# KKK_valdiklis_kopija.net
KiCad netlist of a schematic drawn in EAGLE
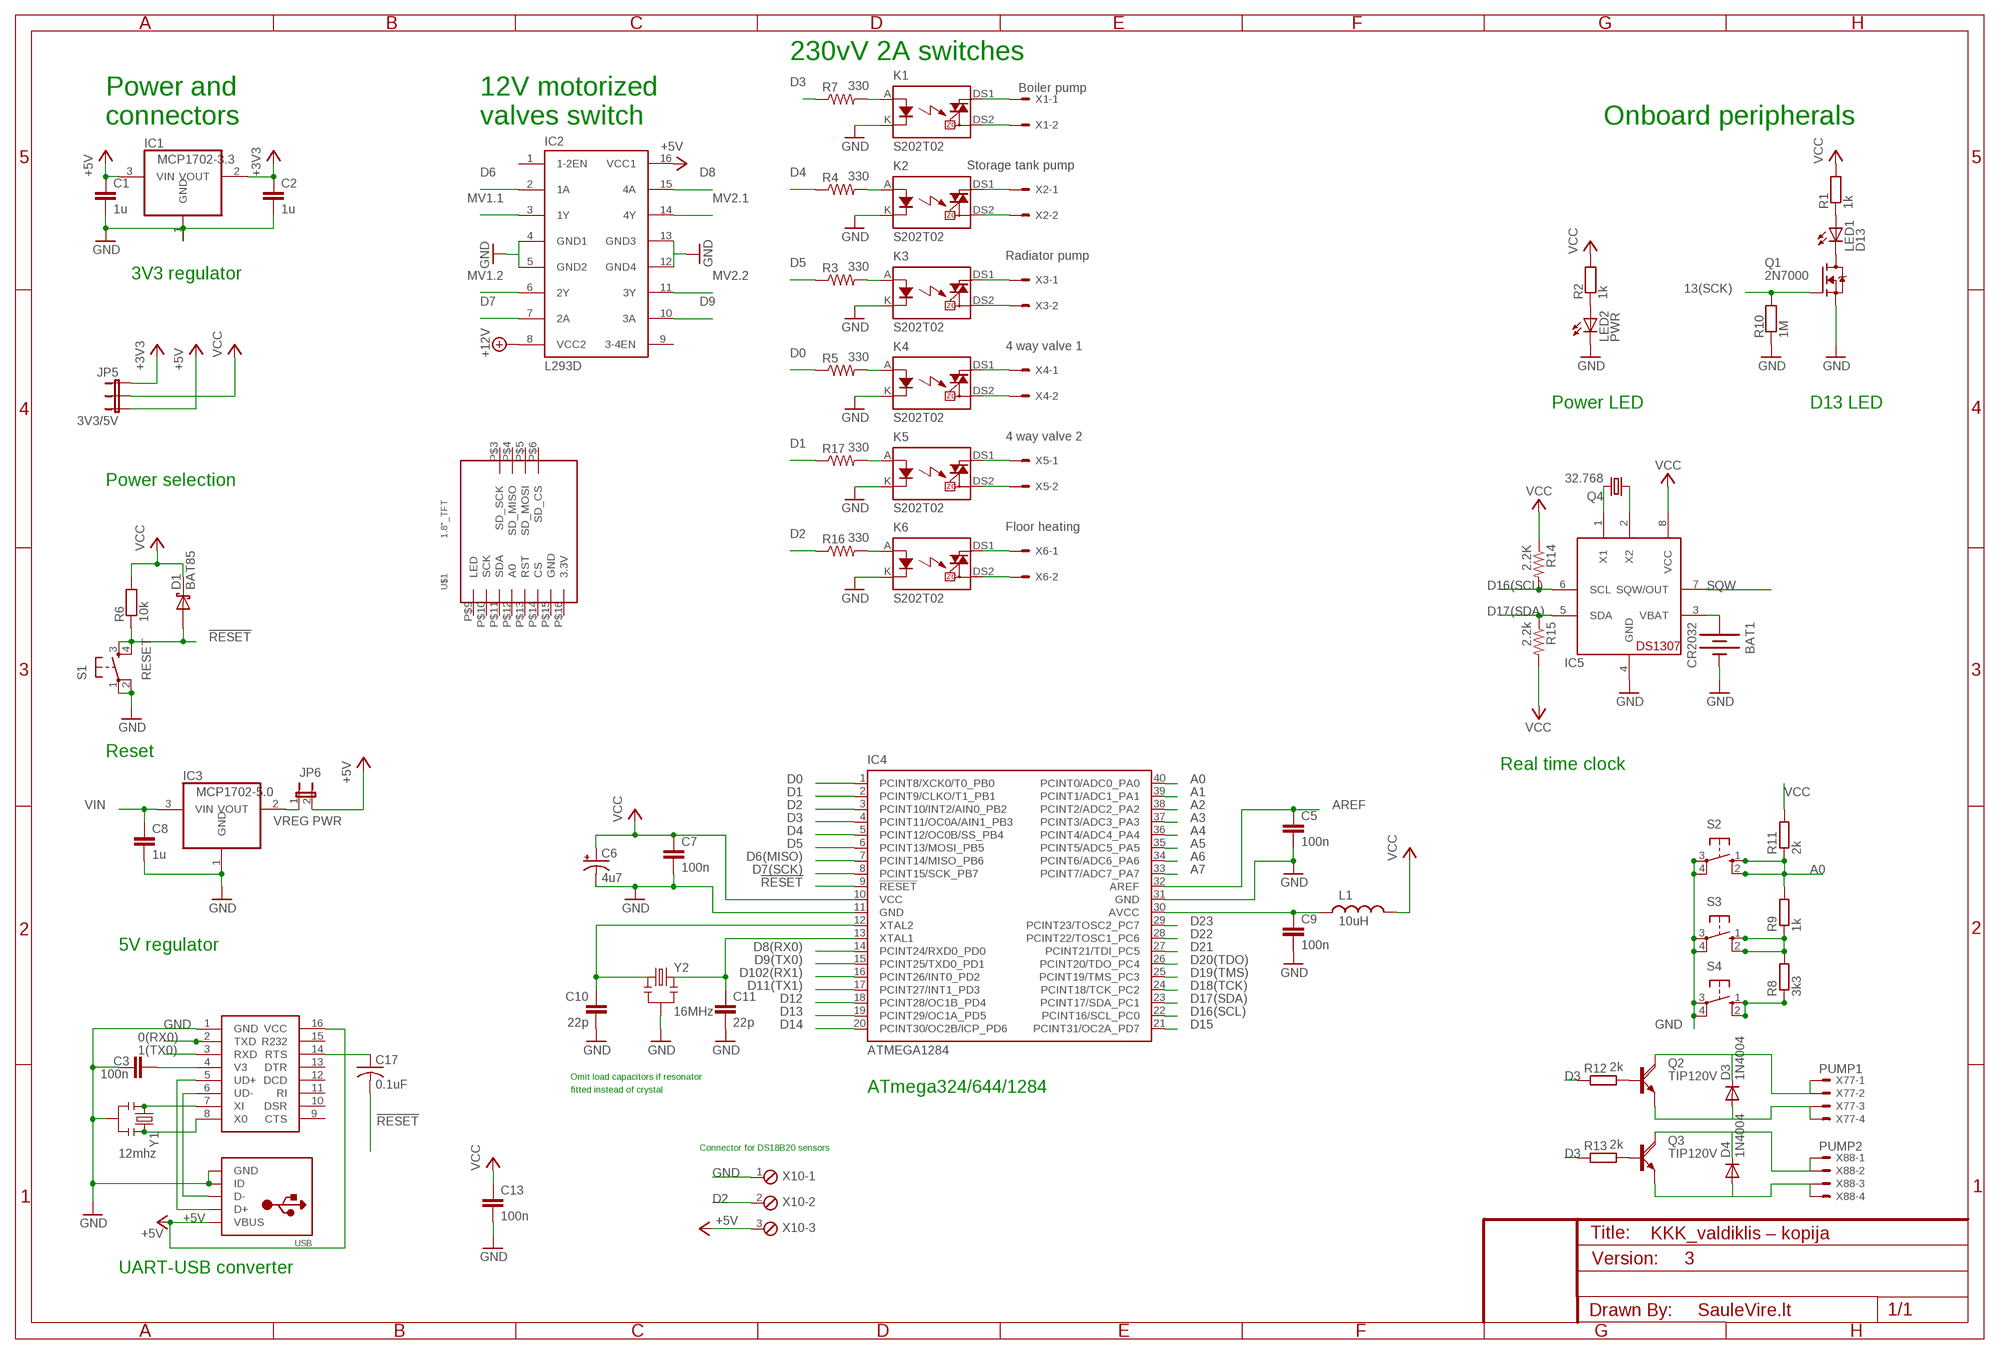
[diagram p0: schematic, sheet 1]

(export (version "E")
  (design (tool "Eeschema 10.0.6"))
  (components
    (comp (ref "BAT1")
      (value "CR2032")
      (footprint "eagle-import:BATTCOM_20MM_PTH")
      (libsource (lib "eagle-import") (part "BATTERY20PTH"))
    )
    (comp (ref "C1")
      (value "1u")
      (footprint "eagle-import:CAP-PTH-5MM")
      (libsource (lib "eagle-import") (part "CAPPTH1"))
    )
    (comp (ref "C2")
      (value "1u")
      (footprint "eagle-import:CAP-PTH-5MM")
      (libsource (lib "eagle-import") (part "CAPPTH1"))
    )
    (comp (ref "C3")
      (value "100n")
      (footprint "eagle-import:CAP-PTH-SMALL")
      (libsource (lib "eagle-import") (part "CAPPTH"))
    )
    (comp (ref "C5")
      (value "100n")
      (footprint "eagle-import:CAP-PTH-SMALL")
      (libsource (lib "eagle-import") (part "CAPPTH"))
    )
    (comp (ref "C6")
      (value "4u7")
      (footprint "eagle-import:CPOL-RADIAL-10UF-25V")
      (libsource (lib "eagle-import") (part "CAP_POLPTH2"))
    )
    (comp (ref "C7")
      (value "100n")
      (footprint "eagle-import:CAP-PTH-SMALL")
      (libsource (lib "eagle-import") (part "CAPPTH"))
    )
    (comp (ref "C8")
      (value "1u")
      (footprint "eagle-import:CAP-PTH-5MM")
      (libsource (lib "eagle-import") (part "CAPPTH1"))
    )
    (comp (ref "C9")
      (value "100n")
      (footprint "eagle-import:CAP-PTH-SMALL")
      (libsource (lib "eagle-import") (part "CAPPTH"))
    )
    (comp (ref "C10")
      (value "22p")
      (footprint "eagle-import:CAP-PTH-SMALL")
      (libsource (lib "eagle-import") (part "CAPPTH"))
    )
    (comp (ref "C11")
      (value "22p")
      (footprint "eagle-import:CAP-PTH-SMALL")
      (libsource (lib "eagle-import") (part "CAPPTH"))
    )
    (comp (ref "C13")
      (value "100n")
      (footprint "eagle-import:CAP-PTH-SMALL")
      (libsource (lib "eagle-import") (part "CAPPTH"))
    )
    (comp (ref "C17")
      (value "0.1uF")
      (footprint "eagle-import:C0805K")
      (libsource (lib "eagle-import") (part "C-USC0805K"))
    )
    (comp (ref "D1")
      (value "BAT85")
      (footprint "eagle-import:DIODE-TH-0.4")
      (libsource (lib "eagle-import") (part "DIODE-SCHOTTKY"))
    )
    (comp (ref "D3")
      (value "1N4004")
      (footprint "eagle-import:DO41-10")
      (libsource (lib "eagle-import") (part "1N4004"))
    )
    (comp (ref "D4")
      (value "1N4004")
      (footprint "eagle-import:DO41-10")
      (libsource (lib "eagle-import") (part "1N4004"))
    )
    (comp (ref "IC1")
      (value "MCP1702-3.3")
      (footprint "eagle-import:SOT223")
      (fields (field (name "MPN") "REG1117"))
      (libsource (lib "eagle-import") (part "REG1117"))
    )
    (comp (ref "IC2")
      (value "L293D")
      (footprint "eagle-import:DIL16")
      (libsource (lib "eagle-import") (part "L293D"))
    )
    (comp (ref "IC3")
      (value "MCP1702-5.0")
      (footprint "eagle-import:SOT223")
      (fields (field (name "MPN") "REG1117"))
      (libsource (lib "eagle-import") (part "REG1117"))
    )
    (comp (ref "IC4")
      (value "ATMEGA1284")
      (footprint "eagle-import:DIL40")
      (fields (field (name "MPN") "ATMEGA644-20PU"))
      (libsource (lib "eagle-import") (part "ATMEGA644-PU20"))
    )
    (comp (ref "IC5")
      (value "DS1307")
      (footprint "eagle-import:DIL08")
      (libsource (lib "eagle-import") (part "DS1307"))
    )
    (comp (ref "JP5")
      (value "3V3/5V")
      (footprint "eagle-import:1X03")
      (libsource (lib "eagle-import") (part "JUMPER-3PTH"))
    )
    (comp (ref "JP6")
      (value "VREG PWR")
      (footprint "eagle-import:1X02")
      (libsource (lib "eagle-import") (part "JUMPER-2PTH"))
    )
    (comp (ref "K1")
      (value "S202T02")
      (footprint "eagle-import:S202T02")
      (libsource (lib "eagle-import") (part "S202T02"))
    )
    (comp (ref "K2")
      (value "S202T02")
      (footprint "eagle-import:S202T02")
      (libsource (lib "eagle-import") (part "S202T02"))
    )
    (comp (ref "K3")
      (value "S202T02")
      (footprint "eagle-import:S202T02")
      (libsource (lib "eagle-import") (part "S202T02"))
    )
    (comp (ref "K4")
      (value "S202T02")
      (footprint "eagle-import:S202T02")
      (libsource (lib "eagle-import") (part "S202T02"))
    )
    (comp (ref "K5")
      (value "S202T02")
      (footprint "eagle-import:S202T02")
      (libsource (lib "eagle-import") (part "S202T02"))
    )
    (comp (ref "K6")
      (value "S202T02")
      (footprint "eagle-import:S202T02")
      (libsource (lib "eagle-import") (part "S202T02"))
    )
    (comp (ref "L1")
      (value "10uH")
      (footprint "eagle-import:RES-AXIAL-0.4")
      (libsource (lib "eagle-import") (part "INDUCTOR0.4{dblquote}-AXIAL"))
    )
    (comp (ref "LED1")
      (value "D13")
      (footprint "eagle-import:LED3MM")
      (libsource (lib "eagle-import") (part "LED3MM"))
    )
    (comp (ref "LED2")
      (value "PWR")
      (footprint "eagle-import:LED3MM")
      (libsource (lib "eagle-import") (part "LED3MM"))
    )
    (comp (ref "Q1")
      (value "2N7000")
      (footprint "eagle-import:TO-92")
      (libsource (lib "eagle-import") (part "2N7000"))
    )
    (comp (ref "Q2")
      (value "TIP120V")
      (footprint "eagle-import:TO220AV")
      (libsource (lib "eagle-import") (part "TIP120V"))
    )
    (comp (ref "Q3")
      (value "TIP120V")
      (footprint "eagle-import:TO220AV")
      (libsource (lib "eagle-import") (part "TIP120V"))
    )
    (comp (ref "Q4")
      (value "32.768")
      (footprint "eagle-import:TC38H")
      (libsource (lib "eagle-import") (part "CRYTALTC38H"))
    )
    (comp (ref "R1")
      (value "1k")
      (footprint "eagle-import:RES-AXIAL-0.4")
      (libsource (lib "eagle-import") (part "RESISTOR"))
    )
    (comp (ref "R2")
      (value "1k")
      (footprint "eagle-import:RES-AXIAL-0.4")
      (libsource (lib "eagle-import") (part "RESISTOR"))
    )
    (comp (ref "R3")
      (value "330")
      (footprint "eagle-import:0207_10")
      (libsource (lib "eagle-import") (part "resistor-1_R-US_0207/10"))
    )
    (comp (ref "R4")
      (value "330")
      (footprint "eagle-import:0207_10")
      (libsource (lib "eagle-import") (part "resistor-1_R-US_0207/10"))
    )
    (comp (ref "R5")
      (value "330")
      (footprint "eagle-import:0207_10")
      (libsource (lib "eagle-import") (part "resistor-1_R-US_0207/10"))
    )
    (comp (ref "R6")
      (value "10k")
      (footprint "eagle-import:RES-AXIAL-0.4")
      (libsource (lib "eagle-import") (part "RESISTOR"))
    )
    (comp (ref "R7")
      (value "330")
      (footprint "eagle-import:0207_10")
      (libsource (lib "eagle-import") (part "resistor-1_R-US_0207/10"))
    )
    (comp (ref "R8")
      (value "3k3")
      (footprint "eagle-import:0207_10")
      (libsource (lib "eagle-import") (part "R-EU_0207/10"))
    )
    (comp (ref "R9")
      (value "1k")
      (footprint "eagle-import:0207_10")
      (libsource (lib "eagle-import") (part "R-EU_0207/10"))
    )
    (comp (ref "R10")
      (value "1M")
      (footprint "eagle-import:RES-AXIAL-0.4")
      (libsource (lib "eagle-import") (part "RESISTOR"))
    )
    (comp (ref "R11")
      (value "2k")
      (footprint "eagle-import:0207_10")
      (libsource (lib "eagle-import") (part "R-EU_0207/10"))
    )
    (comp (ref "R12")
      (value "2k")
      (footprint "eagle-import:0207_10")
      (libsource (lib "eagle-import") (part "R-EU_0207/10"))
    )
    (comp (ref "R13")
      (value "2k")
      (footprint "eagle-import:0207_10")
      (libsource (lib "eagle-import") (part "R-EU_0207/10"))
    )
    (comp (ref "R14")
      (value "2.2K")
      (footprint "eagle-import:0207_10")
      (libsource (lib "eagle-import") (part "R-US_0207/10"))
    )
    (comp (ref "R15")
      (value "2.2k")
      (footprint "eagle-import:0207_10")
      (libsource (lib "eagle-import") (part "R-US_0207/10"))
    )
    (comp (ref "R16")
      (value "330")
      (footprint "eagle-import:0207_10")
      (libsource (lib "eagle-import") (part "resistor-1_R-US_0207/10"))
    )
    (comp (ref "R17")
      (value "330")
      (footprint "eagle-import:0207_10")
      (libsource (lib "eagle-import") (part "resistor-1_R-US_0207/10"))
    )
    (comp (ref "S1")
      (value "RESET")
      (footprint "eagle-import:TACTILE-PTH")
      (libsource (lib "eagle-import") (part "TAC_SWITCHPTH"))
    )
    (comp (ref "S2")
      (value "10-XX")
      (footprint "eagle-import:B3F-10XX")
      (fields (field (name "MPN") "B3F-1000"))
      (libsource (lib "eagle-import") (part "10-XX"))
    )
    (comp (ref "S3")
      (value "10-XX")
      (footprint "eagle-import:B3F-10XX")
      (fields (field (name "MPN") "B3F-1000"))
      (libsource (lib "eagle-import") (part "10-XX"))
    )
    (comp (ref "S4")
      (value "10-XX")
      (footprint "eagle-import:B3F-10XX")
      (fields (field (name "MPN") "B3F-1000"))
      (libsource (lib "eagle-import") (part "10-XX"))
    )
    (comp (ref "U$1")
      (value "1.8\"_TFT")
      (footprint "eagle-import:1.8__TFT")
      (libsource (lib "eagle-import") (part "1.8{dblquote}_TFT"))
    )
    (comp (ref "U$2")
      (value "CH340G")
      (footprint "eagle-import:SO016")
      (libsource (lib "eagle-import") (part "CH340G"))
    )
    (comp (ref "USB")
      (value "USBMOLEX")
      (footprint "eagle-import:USB-MINIB-THM-MOLEX")
      (libsource (lib "eagle-import") (part "USBMOLEX"))
    )
    (comp (ref "X1")
      (value "Boiler pump")
      (footprint "eagle-import:22-23-2021")
      (fields (field (name "MF") "MOLEX") (field (name "MPN") "22-23-2021"))
      (libsource (lib "eagle-import") (part "22-23-2021"))
    )
    (comp (ref "X2")
      (value "Storage tank pump")
      (footprint "eagle-import:22-23-2021")
      (fields (field (name "MF") "MOLEX") (field (name "MPN") "22-23-2021"))
      (libsource (lib "eagle-import") (part "22-23-2021"))
    )
    (comp (ref "X3")
      (value "Radiator pump")
      (footprint "eagle-import:22-23-2021")
      (fields (field (name "MF") "MOLEX") (field (name "MPN") "22-23-2021"))
      (libsource (lib "eagle-import") (part "22-23-2021"))
    )
    (comp (ref "X4")
      (value "4 way valve 1")
      (footprint "eagle-import:22-23-2021")
      (fields (field (name "MF") "MOLEX") (field (name "MPN") "22-23-2021"))
      (libsource (lib "eagle-import") (part "22-23-2021"))
    )
    (comp (ref "X5")
      (value "4 way valve 2")
      (footprint "eagle-import:22-23-2021")
      (fields (field (name "MF") "MOLEX") (field (name "MPN") "22-23-2021"))
      (libsource (lib "eagle-import") (part "22-23-2021"))
    )
    (comp (ref "X6")
      (value "Floor heating")
      (footprint "eagle-import:22-23-2021")
      (fields (field (name "MF") "MOLEX") (field (name "MPN") "22-23-2021"))
      (libsource (lib "eagle-import") (part "22-23-2021"))
    )
    (comp (ref "X10")
      (value "MPT3")
      (footprint "eagle-import:3POL254")
      (libsource (lib "eagle-import") (part "MPT3"))
    )
    (comp (ref "X77")
      (value "PUMP1")
      (footprint "eagle-import:22-23-2041")
      (fields (field (name "MF") "MOLEX") (field (name "MPN") "22-23-2041"))
      (libsource (lib "eagle-import") (part "22-23-2041"))
    )
    (comp (ref "X88")
      (value "PUMP2")
      (footprint "eagle-import:22-23-2041")
      (fields (field (name "MF") "MOLEX") (field (name "MPN") "22-23-2041"))
      (libsource (lib "eagle-import") (part "22-23-2041"))
    )
    (comp (ref "Y1")
      (value "12mhz")
      (footprint "eagle-import:RESONATOR-PTH")
      (libsource (lib "eagle-import") (part "RESONATORPTH"))
    )
    (comp (ref "Y2")
      (value "16MHz")
      (footprint "eagle-import:HC49U-V-RESONATOR")
      (libsource (lib "eagle-import") (part "CRYSTAL-RESONATOR"))
    )
  )
  (nets
    (net (code "1") (name "+3V3") (class "Default")
      (node (ref "C2") (pin "1") (pinfunction "1_1") (pintype "passive"))
      (node (ref "IC1") (pin "2") (pinfunction "VOUT_2") (pintype "output"))
      (node (ref "JP5") (pin "1") (pinfunction "1_1") (pintype "passive"))
    )
    (net (code "2") (name "+5V") (class "Default")
      (node (ref "C1") (pin "1") (pinfunction "1_1") (pintype "passive"))
      (node (ref "IC1") (pin "3") (pinfunction "VIN_3") (pintype "input"))
      (node (ref "IC2") (pin "16") (pinfunction "VCC1_16") (pintype "power_in"))
      (node (ref "JP5") (pin "3") (pinfunction "3_3") (pintype "passive"))
      (node (ref "JP6") (pin "2") (pinfunction "2_2") (pintype "passive"))
      (node (ref "U$2") (pin "16") (pinfunction "VCC_16") (pintype "bidirectional"))
      (node (ref "USB") (pin "VBUS") (pinfunction "VBUS_VBUS") (pintype "power_in"))
      (node (ref "X10") (pin "3") (pinfunction "1_3") (pintype "passive"))
    )
    (net (code "3") (name "+12V") (class "Default")
      (node (ref "IC2") (pin "8") (pinfunction "VCC2_8") (pintype "power_in"))
    )
    (net (code "4") (name "/0(RX0)") (class "Default")
      (node (ref "U$2") (pin "2") (pinfunction "TXD_2") (pintype "bidirectional"))
    )
    (net (code "5") (name "/1(TX0)") (class "Default")
      (node (ref "U$2") (pin "3") (pinfunction "RXD_3") (pintype "bidirectional"))
    )
    (net (code "6") (name "/13(SCK)") (class "Default")
      (node (ref "Q1") (pin "2") (pinfunction "G_2") (pintype "passive"))
      (node (ref "R10") (pin "P$2") (pinfunction "2_P$2") (pintype "passive"))
    )
    (net (code "7") (name "/A0") (class "Default")
      (node (ref "IC4") (pin "40") (pinfunction "PCINT0/ADC0_PA0_40") (pintype "bidirectional"))
      (node (ref "R11") (pin "1") (pinfunction "1_1") (pintype "passive"))
      (node (ref "R9") (pin "2") (pinfunction "2_2") (pintype "passive"))
      (node (ref "S2") (pin "1") (pinfunction "S_1") (pintype "passive"))
      (node (ref "S2") (pin "2") (pinfunction "S1_2") (pintype "passive"))
    )
    (net (code "8") (name "/A1") (class "Default")
      (node (ref "IC4") (pin "39") (pinfunction "PCINT1/ADC1_PA1_39") (pintype "bidirectional"))
    )
    (net (code "9") (name "/A2") (class "Default")
      (node (ref "IC4") (pin "38") (pinfunction "PCINT2/ADC2_PA2_38") (pintype "bidirectional"))
    )
    (net (code "10") (name "/A3") (class "Default")
      (node (ref "IC4") (pin "37") (pinfunction "PCINT3/ADC3_PA3_37") (pintype "bidirectional"))
    )
    (net (code "11") (name "/A4") (class "Default")
      (node (ref "IC4") (pin "36") (pinfunction "PCINT4/ADC4_PA4_36") (pintype "bidirectional"))
    )
    (net (code "12") (name "/A5") (class "Default")
      (node (ref "IC4") (pin "35") (pinfunction "PCINT5/ADC5_PA5_35") (pintype "bidirectional"))
    )
    (net (code "13") (name "/A6") (class "Default")
      (node (ref "IC4") (pin "34") (pinfunction "PCINT6/ADC6_PA6_34") (pintype "bidirectional"))
    )
    (net (code "14") (name "/A7") (class "Default")
      (node (ref "IC4") (pin "33") (pinfunction "PCINT7/ADC7_PA7_33") (pintype "bidirectional"))
    )
    (net (code "15") (name "/AREF") (class "Default")
      (node (ref "C5") (pin "1") (pinfunction "1_1") (pintype "passive"))
      (node (ref "IC4") (pin "32") (pinfunction "AREF_32") (pintype "passive"))
    )
    (net (code "16") (name "/D0") (class "Default")
      (node (ref "IC4") (pin "1") (pinfunction "PCINT8/XCK0/T0_PB0_1") (pintype "bidirectional"))
      (node (ref "R5") (pin "1") (pinfunction "1_1") (pintype "passive"))
    )
    (net (code "17") (name "/D1") (class "Default")
      (node (ref "IC4") (pin "2") (pinfunction "PCINT9/CLKO/T1_PB1_2") (pintype "bidirectional"))
      (node (ref "R17") (pin "1") (pinfunction "1_1") (pintype "passive"))
    )
    (net (code "18") (name "/D2") (class "Default")
      (node (ref "IC4") (pin "3") (pinfunction "PCINT10/INT2/AIN0_PB2_3") (pintype "bidirectional"))
      (node (ref "R16") (pin "1") (pinfunction "1_1") (pintype "passive"))
      (node (ref "X10") (pin "2") (pinfunction "1_2") (pintype "passive"))
    )
    (net (code "19") (name "/D3") (class "Default")
      (node (ref "IC4") (pin "4") (pinfunction "PCINT11/OC0A/AIN1_PB3_4") (pintype "bidirectional"))
      (node (ref "R12") (pin "1") (pinfunction "1_1") (pintype "passive"))
      (node (ref "R13") (pin "1") (pinfunction "1_1") (pintype "passive"))
      (node (ref "R7") (pin "1") (pinfunction "1_1") (pintype "passive"))
    )
    (net (code "20") (name "/D4") (class "Default")
      (node (ref "IC4") (pin "5") (pinfunction "PCINT12/OC0B/SS_PB4_5") (pintype "bidirectional"))
      (node (ref "R4") (pin "1") (pinfunction "1_1") (pintype "passive"))
    )
    (net (code "21") (name "/D5") (class "Default")
      (node (ref "IC4") (pin "6") (pinfunction "PCINT13/MOSI_PB5_6") (pintype "bidirectional"))
      (node (ref "R3") (pin "1") (pinfunction "1_1") (pintype "passive"))
    )
    (net (code "22") (name "/D6") (class "Default")
      (node (ref "IC2") (pin "2") (pinfunction "1A_2") (pintype "input"))
    )
    (net (code "23") (name "/D6(MISO)") (class "Default")
      (node (ref "IC4") (pin "7") (pinfunction "PCINT14/MISO_PB6_7") (pintype "bidirectional"))
    )
    (net (code "24") (name "/D7") (class "Default")
      (node (ref "IC2") (pin "7") (pinfunction "2A_7") (pintype "input"))
    )
    (net (code "25") (name "/D7(SCK)") (class "Default")
      (node (ref "IC4") (pin "8") (pinfunction "PCINT15/SCK_PB7_8") (pintype "bidirectional"))
    )
    (net (code "26") (name "/D8") (class "Default")
      (node (ref "IC2") (pin "15") (pinfunction "4A_15") (pintype "input"))
    )
    (net (code "27") (name "/D8(RX0)") (class "Default")
      (node (ref "IC4") (pin "14") (pinfunction "PCINT24/RXD0_PD0_14") (pintype "bidirectional"))
    )
    (net (code "28") (name "/D9") (class "Default")
      (node (ref "IC2") (pin "10") (pinfunction "3A_10") (pintype "input"))
    )
    (net (code "29") (name "/D9(TX0)") (class "Default")
      (node (ref "IC4") (pin "15") (pinfunction "PCINT25/TXD0_PD1_15") (pintype "bidirectional"))
    )
    (net (code "30") (name "/D11(TX1)") (class "Default")
      (node (ref "IC4") (pin "17") (pinfunction "PCINT27/INT1_PD3_17") (pintype "bidirectional"))
    )
    (net (code "31") (name "/D12") (class "Default")
      (node (ref "IC4") (pin "18") (pinfunction "PCINT28/OC1B_PD4_18") (pintype "bidirectional"))
    )
    (net (code "32") (name "/D13") (class "Default")
      (node (ref "IC4") (pin "19") (pinfunction "PCINT29/OC1A_PD5_19") (pintype "bidirectional"))
    )
    (net (code "33") (name "/D14") (class "Default")
      (node (ref "IC4") (pin "20") (pinfunction "PCINT30/OC2B/ICP_PD6_20") (pintype "bidirectional"))
    )
    (net (code "34") (name "/D15") (class "Default")
      (node (ref "IC4") (pin "21") (pinfunction "PCINT31/OC2A_PD7_21") (pintype "bidirectional"))
    )
    (net (code "35") (name "/D16(SCL)") (class "Default")
      (node (ref "IC4") (pin "22") (pinfunction "PCINT16/SCL_PC0_22") (pintype "bidirectional"))
      (node (ref "IC5") (pin "6") (pinfunction "SCL_6") (pintype "bidirectional"))
      (node (ref "R14") (pin "2") (pinfunction "2_2") (pintype "passive"))
    )
    (net (code "36") (name "/D17(SDA)") (class "Default")
      (node (ref "IC4") (pin "23") (pinfunction "PCINT17/SDA_PC1_23") (pintype "bidirectional"))
      (node (ref "IC5") (pin "5") (pinfunction "SDA_5") (pintype "bidirectional"))
      (node (ref "R15") (pin "1") (pinfunction "1_1") (pintype "passive"))
    )
    (net (code "37") (name "/D18(TCK)") (class "Default")
      (node (ref "IC4") (pin "24") (pinfunction "PCINT18/TCK_PC2_24") (pintype "bidirectional"))
    )
    (net (code "38") (name "/D19(TMS)") (class "Default")
      (node (ref "IC4") (pin "25") (pinfunction "PCINT19/TMS_PC3_25") (pintype "bidirectional"))
    )
    (net (code "39") (name "/D20(TDO)") (class "Default")
      (node (ref "IC4") (pin "26") (pinfunction "PCINT20/TDO_PC4_26") (pintype "bidirectional"))
    )
    (net (code "40") (name "/D21") (class "Default")
      (node (ref "IC4") (pin "27") (pinfunction "PCINT21/TDI_PC5_27") (pintype "bidirectional"))
    )
    (net (code "41") (name "/D22") (class "Default")
      (node (ref "IC4") (pin "28") (pinfunction "PCINT22/TOSC1_PC6_28") (pintype "bidirectional"))
    )
    (net (code "42") (name "/D23") (class "Default")
      (node (ref "IC4") (pin "29") (pinfunction "PCINT23/TOSC2_PC7_29") (pintype "bidirectional"))
    )
    (net (code "43") (name "/D102(RX1)") (class "Default")
      (node (ref "IC4") (pin "16") (pinfunction "PCINT26/INT0_PD2_16") (pintype "bidirectional"))
    )
    (net (code "44") (name "/MV1.1") (class "Default")
      (node (ref "IC2") (pin "3") (pinfunction "1Y_3") (pintype "output"))
    )
    (net (code "45") (name "/MV1.2") (class "Default")
      (node (ref "IC2") (pin "6") (pinfunction "2Y_6") (pintype "output"))
    )
    (net (code "46") (name "/MV2.1") (class "Default")
      (node (ref "IC2") (pin "14") (pinfunction "4Y_14") (pintype "output"))
    )
    (net (code "47") (name "/MV2.2") (class "Default")
      (node (ref "IC2") (pin "11") (pinfunction "3Y_11") (pintype "output"))
    )
    (net (code "48") (name "/SQW") (class "Default")
      (node (ref "IC5") (pin "7") (pinfunction "SQW/OUT_7") (pintype "bidirectional"))
    )
    (net (code "49") (name "/VIN") (class "Default")
      (node (ref "C8") (pin "1") (pinfunction "1_1") (pintype "passive"))
      (node (ref "IC3") (pin "3") (pinfunction "VIN_3") (pintype "input"))
    )
    (net (code "50") (name "/~{RESET}") (class "Default")
      (node (ref "C17") (pin "2") (pinfunction "2_2") (pintype "passive"))
      (node (ref "D1") (pin "A") (pinfunction "A_A") (pintype "passive"))
      (node (ref "IC4") (pin "9") (pinfunction "~{RESET}_9") (pintype "input"))
      (node (ref "R6") (pin "P$1") (pinfunction "1_P$1") (pintype "passive"))
      (node (ref "S1") (pin "3") (pinfunction "3_3") (pintype "passive"))
      (node (ref "S1") (pin "4") (pinfunction "4_4") (pintype "passive"))
    )
    (net (code "51") (name "GND") (class "Default")
      (node (ref "BAT1") (pin "2") (pinfunction "-_2") (pintype "power_in"))
      (node (ref "C1") (pin "2") (pinfunction "2_2") (pintype "passive"))
      (node (ref "C10") (pin "2") (pinfunction "2_2") (pintype "passive"))
      (node (ref "C11") (pin "2") (pinfunction "2_2") (pintype "passive"))
      (node (ref "C13") (pin "2") (pinfunction "2_2") (pintype "passive"))
      (node (ref "C2") (pin "2") (pinfunction "2_2") (pintype "passive"))
      (node (ref "C3") (pin "1") (pinfunction "1_1") (pintype "passive"))
      (node (ref "C5") (pin "2") (pinfunction "2_2") (pintype "passive"))
      (node (ref "C6") (pin "2") (pinfunction "-_2") (pintype "passive"))
      (node (ref "C7") (pin "2") (pinfunction "2_2") (pintype "passive"))
      (node (ref "C8") (pin "2") (pinfunction "2_2") (pintype "passive"))
      (node (ref "C9") (pin "2") (pinfunction "2_2") (pintype "passive"))
      (node (ref "D3") (pin "A") (pinfunction "A_A") (pintype "passive"))
      (node (ref "IC1") (pin "1") (pinfunction "GND_1") (pintype "power_in"))
      (node (ref "IC2") (pin "12") (pinfunction "GND4_12") (pintype "power_in"))
      (node (ref "IC2") (pin "13") (pinfunction "GND3_13") (pintype "power_in"))
      (node (ref "IC2") (pin "4") (pinfunction "GND1_4") (pintype "power_in"))
      (node (ref "IC2") (pin "5") (pinfunction "GND2_5") (pintype "power_in"))
      (node (ref "IC3") (pin "1") (pinfunction "GND_1") (pintype "power_in"))
      (node (ref "IC4") (pin "11") (pinfunction "GND_11") (pintype "power_in"))
      (node (ref "IC4") (pin "31") (pinfunction "GND_31") (pintype "power_in"))
      (node (ref "IC5") (pin "4") (pinfunction "GND_4") (pintype "power_in"))
      (node (ref "K1") (pin "K") (pinfunction "K_K") (pintype "passive"))
      (node (ref "K2") (pin "K") (pinfunction "K_K") (pintype "passive"))
      (node (ref "K3") (pin "K") (pinfunction "K_K") (pintype "passive"))
      (node (ref "K4") (pin "K") (pinfunction "K_K") (pintype "passive"))
      (node (ref "K5") (pin "K") (pinfunction "K_K") (pintype "passive"))
      (node (ref "K6") (pin "K") (pinfunction "K_K") (pintype "passive"))
      (node (ref "LED2") (pin "K") (pinfunction "C_K") (pintype "passive"))
      (node (ref "Q1") (pin "1") (pinfunction "S_1") (pintype "passive"))
      (node (ref "Q2") (pin "E") (pinfunction "E_E") (pintype "passive"))
      (node (ref "R10") (pin "P$1") (pinfunction "1_P$1") (pintype "passive"))
      (node (ref "S1") (pin "1") (pinfunction "1_1") (pintype "passive"))
      (node (ref "S1") (pin "2") (pinfunction "2_2") (pintype "passive"))
      (node (ref "S2") (pin "3") (pinfunction "P_3") (pintype "passive"))
      (node (ref "S2") (pin "4") (pinfunction "P1_4") (pintype "passive"))
      (node (ref "S3") (pin "3") (pinfunction "P_3") (pintype "passive"))
      (node (ref "S3") (pin "4") (pinfunction "P1_4") (pintype "passive"))
      (node (ref "S4") (pin "3") (pinfunction "P_3") (pintype "passive"))
      (node (ref "S4") (pin "4") (pinfunction "P1_4") (pintype "passive"))
      (node (ref "U$2") (pin "1") (pinfunction "GND_1") (pintype "bidirectional"))
      (node (ref "USB") (pin "GND") (pinfunction "GND_GND") (pintype "power_in"))
      (node (ref "USB") (pin "ID") (pinfunction "ID_ID") (pintype "bidirectional"))
      (node (ref "X10") (pin "1") (pinfunction "1_1") (pintype "passive"))
      (node (ref "X77") (pin "3") (pinfunction "S_3") (pintype "passive"))
      (node (ref "X77") (pin "4") (pinfunction "S_4") (pintype "passive"))
      (node (ref "Y1") (pin "2") (pinfunction "2_2") (pintype "passive"))
      (node (ref "Y2") (pin "GND") (pinfunction "2_GND") (pintype "passive"))
    )
    (net (code "52") (name "Net-(BAT1-+)") (class "Default")
      (node (ref "BAT1") (pin "1") (pinfunction "+_1") (pintype "power_in"))
      (node (ref "IC5") (pin "3") (pinfunction "VBAT_3") (pintype "power_in"))
    )
    (net (code "53") (name "Net-(IC3-VOUT)") (class "Default")
      (node (ref "IC3") (pin "2") (pinfunction "VOUT_2") (pintype "output"))
      (node (ref "JP6") (pin "1") (pinfunction "1_1") (pintype "passive"))
    )
    (net (code "54") (name "Net-(IC4-AVCC)") (class "Default")
      (node (ref "C9") (pin "1") (pinfunction "1_1") (pintype "passive"))
      (node (ref "IC4") (pin "30") (pinfunction "AVCC_30") (pintype "power_in"))
      (node (ref "L1") (pin "P$1") (pinfunction "1_P$1") (pintype "passive"))
    )
    (net (code "55") (name "Net-(IC4-XTAL1)") (class "Default")
      (node (ref "C11") (pin "1") (pinfunction "1_1") (pintype "passive"))
      (node (ref "IC4") (pin "13") (pinfunction "XTAL1_13") (pintype "input"))
      (node (ref "Y2") (pin "2") (pinfunction "3_2") (pintype "passive"))
    )
    (net (code "56") (name "Net-(IC4-XTAL2)") (class "Default")
      (node (ref "C10") (pin "1") (pinfunction "1_1") (pintype "passive"))
      (node (ref "IC4") (pin "12") (pinfunction "XTAL2_12") (pintype "output"))
      (node (ref "Y2") (pin "1") (pinfunction "1_1") (pintype "passive"))
    )
    (net (code "57") (name "Net-(IC5-X1)") (class "Default")
      (node (ref "IC5") (pin "1") (pinfunction "X1_1") (pintype "passive"))
      (node (ref "Q4") (pin "2") (pinfunction "2_2") (pintype "passive"))
    )
    (net (code "58") (name "Net-(IC5-X2)") (class "Default")
      (node (ref "IC5") (pin "2") (pinfunction "X2_2") (pintype "passive"))
      (node (ref "Q4") (pin "1") (pinfunction "1_1") (pintype "passive"))
    )
    (net (code "59") (name "Net-(K1-PadA)") (class "Default")
      (node (ref "K1") (pin "A") (pinfunction "A_A") (pintype "passive"))
      (node (ref "R7") (pin "2") (pinfunction "2_2") (pintype "passive"))
    )
    (net (code "60") (name "Net-(K2-PadA)") (class "Default")
      (node (ref "K2") (pin "A") (pinfunction "A_A") (pintype "passive"))
      (node (ref "R4") (pin "2") (pinfunction "2_2") (pintype "passive"))
    )
    (net (code "61") (name "Net-(K3-PadA)") (class "Default")
      (node (ref "K3") (pin "A") (pinfunction "A_A") (pintype "passive"))
      (node (ref "R3") (pin "2") (pinfunction "2_2") (pintype "passive"))
    )
    (net (code "62") (name "Net-(K4-PadA)") (class "Default")
      (node (ref "K4") (pin "A") (pinfunction "A_A") (pintype "passive"))
      (node (ref "R5") (pin "2") (pinfunction "2_2") (pintype "passive"))
    )
    (net (code "63") (name "Net-(K5-PadA)") (class "Default")
      (node (ref "K5") (pin "A") (pinfunction "A_A") (pintype "passive"))
      (node (ref "R17") (pin "2") (pinfunction "2_2") (pintype "passive"))
    )
    (net (code "64") (name "Net-(K6-PadA)") (class "Default")
      (node (ref "K6") (pin "A") (pinfunction "A_A") (pintype "passive"))
      (node (ref "R16") (pin "2") (pinfunction "2_2") (pintype "passive"))
    )
    (net (code "65") (name "Net-(LED1-C)") (class "Default")
      (node (ref "LED1") (pin "K") (pinfunction "C_K") (pintype "passive"))
      (node (ref "Q1") (pin "3") (pinfunction "D_3") (pintype "passive"))
    )
    (net (code "66") (name "Net-(Q2-PadB)") (class "Default")
      (node (ref "Q2") (pin "B") (pinfunction "B_B") (pintype "passive"))
      (node (ref "R12") (pin "2") (pinfunction "2_2") (pintype "passive"))
    )
    (net (code "67") (name "Net-(Q3-PadB)") (class "Default")
      (node (ref "Q3") (pin "B") (pinfunction "B_B") (pintype "passive"))
      (node (ref "R13") (pin "2") (pinfunction "2_2") (pintype "passive"))
    )
    (net (code "68") (name "Net-(R1-1)") (class "Default")
      (node (ref "LED1") (pin "A") (pinfunction "A_A") (pintype "passive"))
      (node (ref "R1") (pin "P$1") (pinfunction "1_P$1") (pintype "passive"))
    )
    (net (code "69") (name "Net-(R2-1)") (class "Default")
      (node (ref "LED2") (pin "A") (pinfunction "A_A") (pintype "passive"))
      (node (ref "R2") (pin "P$1") (pinfunction "1_P$1") (pintype "passive"))
    )
    (net (code "70") (name "Net-(S3-S)") (class "Default")
      (node (ref "R8") (pin "2") (pinfunction "2_2") (pintype "passive"))
      (node (ref "R9") (pin "1") (pinfunction "1_1") (pintype "passive"))
      (node (ref "S3") (pin "1") (pinfunction "S_1") (pintype "passive"))
      (node (ref "S3") (pin "2") (pinfunction "S1_2") (pintype "passive"))
    )
    (net (code "71") (name "Net-(S4-S)") (class "Default")
      (node (ref "R8") (pin "1") (pinfunction "1_1") (pintype "passive"))
      (node (ref "S4") (pin "1") (pinfunction "S_1") (pintype "passive"))
      (node (ref "S4") (pin "2") (pinfunction "S1_2") (pintype "passive"))
    )
    (net (code "72") (name "Net-(U$2-RTS)") (class "Default")
      (node (ref "C17") (pin "1") (pinfunction "1_1") (pintype "passive"))
      (node (ref "U$2") (pin "14") (pinfunction "RTS_14") (pintype "bidirectional"))
    )
    (net (code "73") (name "Net-(U$2-UD+)") (class "Default")
      (node (ref "U$2") (pin "5") (pinfunction "UD+_5") (pintype "bidirectional"))
      (node (ref "USB") (pin "D+") (pinfunction "D+_D+") (pintype "bidirectional"))
    )
    (net (code "74") (name "Net-(U$2-UD-)") (class "Default")
      (node (ref "U$2") (pin "6") (pinfunction "UD-_6") (pintype "bidirectional"))
      (node (ref "USB") (pin "D-") (pinfunction "D-_D-") (pintype "bidirectional"))
    )
    (net (code "75") (name "Net-(U$2-V3)") (class "Default")
      (node (ref "C3") (pin "2") (pinfunction "2_2") (pintype "passive"))
      (node (ref "U$2") (pin "4") (pinfunction "V3_4") (pintype "bidirectional"))
    )
    (net (code "76") (name "Net-(U$2-X0)") (class "Default")
      (node (ref "U$2") (pin "8") (pinfunction "X0_8") (pintype "bidirectional"))
      (node (ref "Y1") (pin "3") (pinfunction "3_3") (pintype "passive"))
    )
    (net (code "77") (name "Net-(U$2-XI)") (class "Default")
      (node (ref "U$2") (pin "7") (pinfunction "XI_7") (pintype "bidirectional"))
      (node (ref "Y1") (pin "1") (pinfunction "1_1") (pintype "passive"))
    )
    (net (code "78") (name "Net-(X1A-S)") (class "Default")
      (node (ref "K1") (pin "DS1") (pinfunction "DS1_DS1") (pintype "passive"))
      (node (ref "X1") (pin "1") (pinfunction "S_1") (pintype "passive"))
    )
    (net (code "79") (name "Net-(X1B-S)") (class "Default")
      (node (ref "K1") (pin "DS2") (pinfunction "DS2_DS2") (pintype "passive"))
      (node (ref "X1") (pin "2") (pinfunction "S_2") (pintype "passive"))
    )
    (net (code "80") (name "Net-(X2A-S)") (class "Default")
      (node (ref "K2") (pin "DS1") (pinfunction "DS1_DS1") (pintype "passive"))
      (node (ref "X2") (pin "1") (pinfunction "S_1") (pintype "passive"))
    )
    (net (code "81") (name "Net-(X2B-S)") (class "Default")
      (node (ref "K2") (pin "DS2") (pinfunction "DS2_DS2") (pintype "passive"))
      (node (ref "X2") (pin "2") (pinfunction "S_2") (pintype "passive"))
    )
    (net (code "82") (name "Net-(X3A-S)") (class "Default")
      (node (ref "K3") (pin "DS1") (pinfunction "DS1_DS1") (pintype "passive"))
      (node (ref "X3") (pin "1") (pinfunction "S_1") (pintype "passive"))
    )
    (net (code "83") (name "Net-(X3B-S)") (class "Default")
      (node (ref "K3") (pin "DS2") (pinfunction "DS2_DS2") (pintype "passive"))
      (node (ref "X3") (pin "2") (pinfunction "S_2") (pintype "passive"))
    )
    (net (code "84") (name "Net-(X4A-S)") (class "Default")
      (node (ref "K4") (pin "DS1") (pinfunction "DS1_DS1") (pintype "passive"))
      (node (ref "X4") (pin "1") (pinfunction "S_1") (pintype "passive"))
    )
    (net (code "85") (name "Net-(X4B-S)") (class "Default")
      (node (ref "K4") (pin "DS2") (pinfunction "DS2_DS2") (pintype "passive"))
      (node (ref "X4") (pin "2") (pinfunction "S_2") (pintype "passive"))
    )
    (net (code "86") (name "Net-(X5A-S)") (class "Default")
      (node (ref "K5") (pin "DS1") (pinfunction "DS1_DS1") (pintype "passive"))
      (node (ref "X5") (pin "1") (pinfunction "S_1") (pintype "passive"))
    )
    (net (code "87") (name "Net-(X5B-S)") (class "Default")
      (node (ref "K5") (pin "DS2") (pinfunction "DS2_DS2") (pintype "passive"))
      (node (ref "X5") (pin "2") (pinfunction "S_2") (pintype "passive"))
    )
    (net (code "88") (name "Net-(X6A-S)") (class "Default")
      (node (ref "K6") (pin "DS1") (pinfunction "DS1_DS1") (pintype "passive"))
      (node (ref "X6") (pin "1") (pinfunction "S_1") (pintype "passive"))
    )
    (net (code "89") (name "Net-(X6B-S)") (class "Default")
      (node (ref "K6") (pin "DS2") (pinfunction "DS2_DS2") (pintype "passive"))
      (node (ref "X6") (pin "2") (pinfunction "S_2") (pintype "passive"))
    )
    (net (code "90") (name "Net-(X77A-S)") (class "Default")
      (node (ref "D3") (pin "C") (pinfunction "C_C") (pintype "passive"))
      (node (ref "Q2") (pin "C") (pinfunction "C_C") (pintype "passive"))
      (node (ref "X77") (pin "1") (pinfunction "S_1") (pintype "passive"))
      (node (ref "X77") (pin "2") (pinfunction "S_2") (pintype "passive"))
    )
    (net (code "91") (name "Net-(X88A-S)") (class "Default")
      (node (ref "D4") (pin "C") (pinfunction "C_C") (pintype "passive"))
      (node (ref "Q3") (pin "C") (pinfunction "C_C") (pintype "passive"))
      (node (ref "X88") (pin "1") (pinfunction "S_1") (pintype "passive"))
      (node (ref "X88") (pin "2") (pinfunction "S_2") (pintype "passive"))
    )
    (net (code "92") (name "Net-(X88C-S)") (class "Default")
      (node (ref "D4") (pin "A") (pinfunction "A_A") (pintype "passive"))
      (node (ref "Q3") (pin "E") (pinfunction "E_E") (pintype "passive"))
      (node (ref "X88") (pin "3") (pinfunction "S_3") (pintype "passive"))
      (node (ref "X88") (pin "4") (pinfunction "S_4") (pintype "passive"))
    )
    (net (code "93") (name "VCC") (class "Default")
      (node (ref "C13") (pin "1") (pinfunction "1_1") (pintype "passive"))
      (node (ref "C6") (pin "1") (pinfunction "+_1") (pintype "passive"))
      (node (ref "C7") (pin "1") (pinfunction "1_1") (pintype "passive"))
      (node (ref "D1") (pin "C") (pinfunction "C_C") (pintype "passive"))
      (node (ref "IC4") (pin "10") (pinfunction "VCC_10") (pintype "power_in"))
      (node (ref "IC5") (pin "8") (pinfunction "VCC_8") (pintype "power_in"))
      (node (ref "JP5") (pin "2") (pinfunction "2_2") (pintype "passive"))
      (node (ref "L1") (pin "P$2") (pinfunction "2_P$2") (pintype "passive"))
      (node (ref "R1") (pin "P$2") (pinfunction "2_P$2") (pintype "passive"))
      (node (ref "R11") (pin "2") (pinfunction "2_2") (pintype "passive"))
      (node (ref "R14") (pin "1") (pinfunction "1_1") (pintype "passive"))
      (node (ref "R15") (pin "2") (pinfunction "2_2") (pintype "passive"))
      (node (ref "R2") (pin "P$2") (pinfunction "2_P$2") (pintype "passive"))
      (node (ref "R6") (pin "P$2") (pinfunction "2_P$2") (pintype "passive"))
    )
    (net (code "94") (name "unconnected-(IC2-1-2EN-Pad1)") (class "Default")
      (node (ref "IC2") (pin "1") (pinfunction "1-2EN_1") (pintype "input"))
    )
    (net (code "95") (name "unconnected-(IC2-3-4EN-Pad9)") (class "Default")
      (node (ref "IC2") (pin "9") (pinfunction "3-4EN_9") (pintype "input"))
    )
    (net (code "96") (name "unconnected-(U$1-3.3V-PadP$16)") (class "Default")
      (node (ref "U$1") (pin "P$16") (pinfunction "3.3V_P$16") (pintype "bidirectional"))
    )
    (net (code "97") (name "unconnected-(U$1-A0-PadP$12)") (class "Default")
      (node (ref "U$1") (pin "P$12") (pinfunction "A0_P$12") (pintype "bidirectional"))
    )
    (net (code "98") (name "unconnected-(U$1-CS-PadP$14)") (class "Default")
      (node (ref "U$1") (pin "P$14") (pinfunction "CS_P$14") (pintype "bidirectional"))
    )
    (net (code "99") (name "unconnected-(U$1-GND-PadP$15)") (class "Default")
      (node (ref "U$1") (pin "P$15") (pinfunction "GND_P$15") (pintype "bidirectional"))
    )
    (net (code "100") (name "unconnected-(U$1-LED-PadP$9)") (class "Default")
      (node (ref "U$1") (pin "P$9") (pinfunction "LED_P$9") (pintype "bidirectional"))
    )
    (net (code "101") (name "unconnected-(U$1-RST-PadP$13)") (class "Default")
      (node (ref "U$1") (pin "P$13") (pinfunction "RST_P$13") (pintype "bidirectional"))
    )
    (net (code "102") (name "unconnected-(U$1-SCK-PadP$10)") (class "Default")
      (node (ref "U$1") (pin "P$10") (pinfunction "SCK_P$10") (pintype "bidirectional"))
    )
    (net (code "103") (name "unconnected-(U$1-SDA-PadP$11)") (class "Default")
      (node (ref "U$1") (pin "P$11") (pinfunction "SDA_P$11") (pintype "bidirectional"))
    )
    (net (code "104") (name "unconnected-(U$1-SD_CS-PadP$6)") (class "Default")
      (node (ref "U$1") (pin "P$6") (pinfunction "SD_CS_P$6") (pintype "bidirectional"))
    )
    (net (code "105") (name "unconnected-(U$1-SD_MISO-PadP$4)") (class "Default")
      (node (ref "U$1") (pin "P$4") (pinfunction "SD_MISO_P$4") (pintype "bidirectional"))
    )
    (net (code "106") (name "unconnected-(U$1-SD_MOSI-PadP$5)") (class "Default")
      (node (ref "U$1") (pin "P$5") (pinfunction "SD_MOSI_P$5") (pintype "bidirectional"))
    )
    (net (code "107") (name "unconnected-(U$1-SD_SCK-PadP$3)") (class "Default")
      (node (ref "U$1") (pin "P$3") (pinfunction "SD_SCK_P$3") (pintype "bidirectional"))
    )
    (net (code "108") (name "unconnected-(U$2-CTS-Pad9)") (class "Default")
      (node (ref "U$2") (pin "9") (pinfunction "CTS_9") (pintype "bidirectional"))
    )
    (net (code "109") (name "unconnected-(U$2-DCD-Pad12)") (class "Default")
      (node (ref "U$2") (pin "12") (pinfunction "DCD_12") (pintype "bidirectional"))
    )
    (net (code "110") (name "unconnected-(U$2-DSR-Pad10)") (class "Default")
      (node (ref "U$2") (pin "10") (pinfunction "DSR_10") (pintype "bidirectional"))
    )
    (net (code "111") (name "unconnected-(U$2-DTR-Pad13)") (class "Default")
      (node (ref "U$2") (pin "13") (pinfunction "DTR_13") (pintype "bidirectional"))
    )
    (net (code "112") (name "unconnected-(U$2-R232-Pad15)") (class "Default")
      (node (ref "U$2") (pin "15") (pinfunction "R232_15") (pintype "bidirectional"))
    )
    (net (code "113") (name "unconnected-(U$2-RI-Pad11)") (class "Default")
      (node (ref "U$2") (pin "11") (pinfunction "RI_11") (pintype "bidirectional"))
    )
  )
)
